# Barrido_doble_de_fuente_DC.net
KiCad netlist of a schematic drawn in Altium Designer
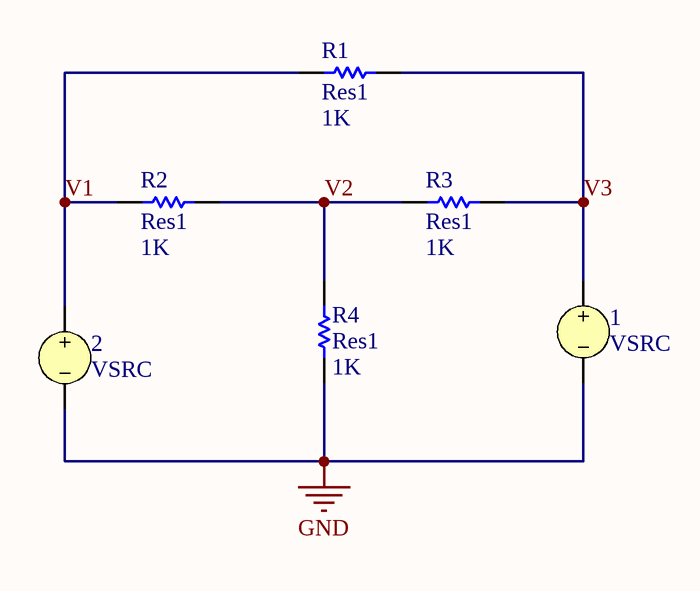
[diagram p0: Barrido doble de fuente DC.SchDoc]

(export (version "E")
  (design (tool "Eeschema 10.0.6"))
  (components
    (comp (ref "1")
      (value "VSRC")
      (description "Voltage Source")
      (fields (field (name "PUBLISHER") "Altium Limited"))
      (libsource (lib "Simulation Sources") (part "VSRC"))
    )
    (comp (ref "2")
      (value "VSRC")
      (description "Voltage Source")
      (fields (field (name "PUBLISHER") "Altium Limited"))
      (libsource (lib "Simulation Sources") (part "VSRC"))
    )
    (comp (ref "R1")
      (value "Res1")
      (footprint "AXIAL-0.3")
      (description "Resistor")
      (fields (field (name "ALTIUM_VALUE") "1K") (field (name "PUBLISHER") "Altium Limited"))
      (libsource (lib "Miscellaneous Devices") (part "Res1"))
    )
    (comp (ref "R2")
      (value "Res1")
      (footprint "AXIAL-0.3")
      (description "Resistor")
      (fields (field (name "ALTIUM_VALUE") "1K") (field (name "PUBLISHER") "Altium Limited"))
      (libsource (lib "Miscellaneous Devices") (part "Res1"))
    )
    (comp (ref "R3")
      (value "Res1")
      (footprint "AXIAL-0.3")
      (description "Resistor")
      (fields (field (name "ALTIUM_VALUE") "1K") (field (name "PUBLISHER") "Altium Limited"))
      (libsource (lib "Miscellaneous Devices") (part "Res1"))
    )
    (comp (ref "R4")
      (value "Res1")
      (footprint "AXIAL-0.3")
      (description "Resistor")
      (fields (field (name "ALTIUM_VALUE") "1K") (field (name "PUBLISHER") "Altium Limited"))
      (libsource (lib "Miscellaneous Devices") (part "Res1"))
    )
  )
  (nets
    (net (code "1") (name "/V1") (class "Default")
      (node (ref "2") (pin "1") (pinfunction "1_1") (pintype "passive"))
      (node (ref "R1") (pin "2") (pinfunction "2_2") (pintype "passive"))
      (node (ref "R2") (pin "1") (pinfunction "1_1") (pintype "passive"))
    )
    (net (code "2") (name "/V2") (class "Default")
      (node (ref "R2") (pin "2") (pinfunction "2_2") (pintype "passive"))
      (node (ref "R3") (pin "2") (pinfunction "2_2") (pintype "passive"))
      (node (ref "R4") (pin "1") (pinfunction "1_1") (pintype "passive"))
    )
    (net (code "3") (name "/V3") (class "Default")
      (node (ref "1") (pin "1") (pinfunction "1_1") (pintype "passive"))
      (node (ref "R1") (pin "1") (pinfunction "1_1") (pintype "passive"))
      (node (ref "R3") (pin "1") (pinfunction "1_1") (pintype "passive"))
    )
    (net (code "4") (name "GND") (class "Default")
      (node (ref "1") (pin "2") (pinfunction "2_2") (pintype "passive"))
      (node (ref "2") (pin "2") (pinfunction "2_2") (pintype "passive"))
      (node (ref "R4") (pin "2") (pinfunction "2_2") (pintype "passive"))
    )
  )
)
